# unoedge_v2.net
KiCad netlist of a schematic drawn in EAGLE
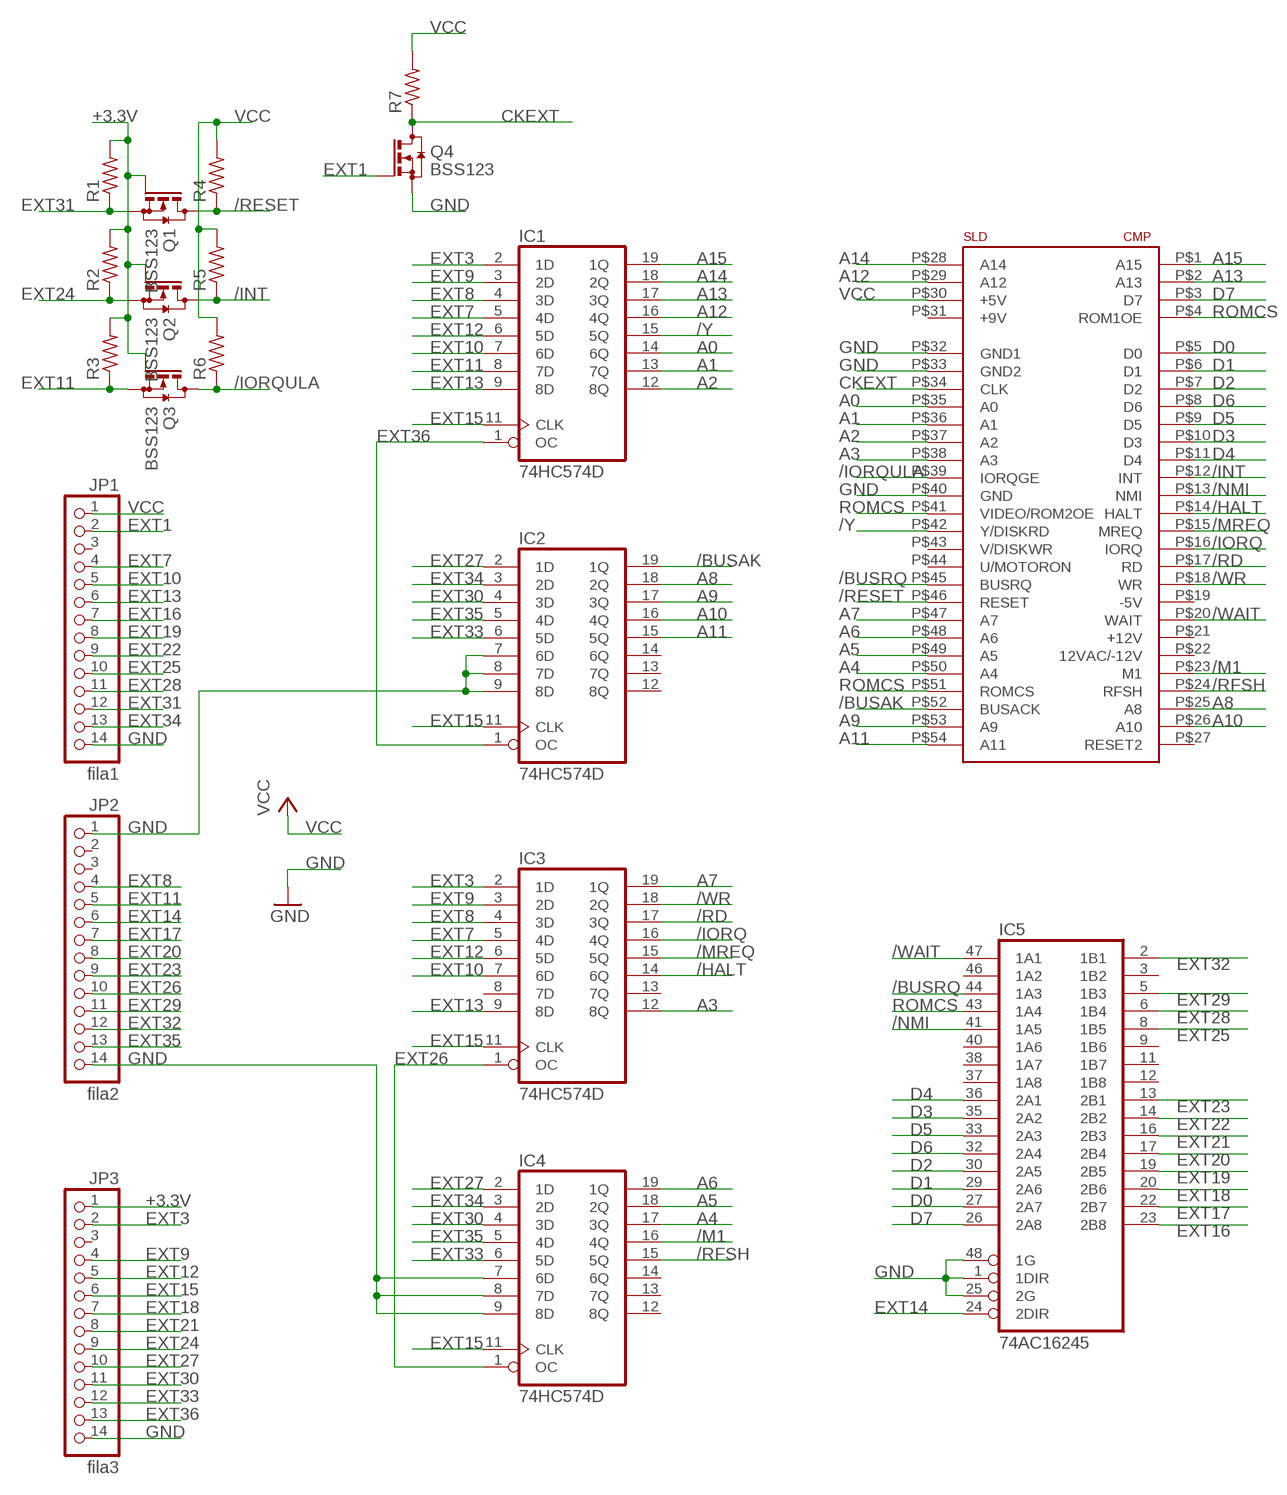
[diagram p0: schematic, sheet 1]

(export (version "E")
  (design (tool "Eeschema 10.0.6"))
  (components
    (comp (ref "IC1")
      (value "74HC574D")
      (footprint "eagle-import:SO20W")
      (libsource (lib "eagle-import") (part "74574DHC"))
    )
    (comp (ref "IC2")
      (value "74HC574D")
      (footprint "eagle-import:SO20W")
      (libsource (lib "eagle-import") (part "74574DHC"))
    )
    (comp (ref "IC3")
      (value "74HC574D")
      (footprint "eagle-import:SO20W")
      (libsource (lib "eagle-import") (part "74574DHC"))
    )
    (comp (ref "IC4")
      (value "74HC574D")
      (footprint "eagle-import:SO20W")
      (libsource (lib "eagle-import") (part "74574DHC"))
    )
    (comp (ref "IC5")
      (value "74AC16245")
      (footprint "eagle-import:SSOP48DL")
      (libsource (lib "eagle-import") (part "74AC16245"))
    )
    (comp (ref "JP1")
      (value "fila1")
      (footprint "eagle-import:1X14")
      (libsource (lib "eagle-import") (part "PINHD-1X14"))
    )
    (comp (ref "JP2")
      (value "fila2")
      (footprint "eagle-import:1X14")
      (libsource (lib "eagle-import") (part "PINHD-1X14"))
    )
    (comp (ref "JP3")
      (value "fila3")
      (footprint "eagle-import:1X14")
      (libsource (lib "eagle-import") (part "PINHD-1X14"))
    )
    (comp (ref "Q1")
      (value "BSS123")
      (footprint "eagle-import:SOT23")
      (libsource (lib "eagle-import") (part "BSS123"))
    )
    (comp (ref "Q2")
      (value "BSS123")
      (footprint "eagle-import:SOT23")
      (libsource (lib "eagle-import") (part "BSS123"))
    )
    (comp (ref "Q3")
      (value "BSS123")
      (footprint "eagle-import:SOT23")
      (libsource (lib "eagle-import") (part "BSS123"))
    )
    (comp (ref "Q4")
      (value "BSS123")
      (footprint "eagle-import:SOT23")
      (libsource (lib "eagle-import") (part "BSS123"))
    )
    (comp (ref "R1")
      (value "R-US_M0805")
      (footprint "eagle-import:M0805")
      (libsource (lib "eagle-import") (part "R-US_M0805"))
    )
    (comp (ref "R2")
      (value "R-US_M0805")
      (footprint "eagle-import:M0805")
      (libsource (lib "eagle-import") (part "R-US_M0805"))
    )
    (comp (ref "R3")
      (value "R-US_M0805")
      (footprint "eagle-import:M0805")
      (libsource (lib "eagle-import") (part "R-US_M0805"))
    )
    (comp (ref "R4")
      (value "R-US_M0805")
      (footprint "eagle-import:M0805")
      (libsource (lib "eagle-import") (part "R-US_M0805"))
    )
    (comp (ref "R5")
      (value "R-US_M0805")
      (footprint "eagle-import:M0805")
      (libsource (lib "eagle-import") (part "R-US_M0805"))
    )
    (comp (ref "R6")
      (value "R-US_M0805")
      (footprint "eagle-import:M0805")
      (libsource (lib "eagle-import") (part "R-US_M0805"))
    )
    (comp (ref "R7")
      (value "R-US_M0805")
      (footprint "eagle-import:M0805")
      (libsource (lib "eagle-import") (part "R-US_M0805"))
    )
    (comp (ref "U$2")
      (value "CONECTOR_EDGE_LADO_SPECTRUM")
      (footprint "eagle-import:CONECTOR_LADO_SPECTRUM")
      (libsource (lib "eagle-import") (part "CONECTOR_EDGE_LADO_SPECTRUM"))
    )
  )
  (nets
    (net (code "1") (name "/+3.3V") (class "Default")
      (node (ref "JP3") (pin "1") (pinfunction "1_1") (pintype "passive"))
      (node (ref "Q1") (pin "1") (pinfunction "G_1") (pintype "passive"))
      (node (ref "Q2") (pin "1") (pinfunction "G_1") (pintype "passive"))
      (node (ref "Q3") (pin "1") (pinfunction "G_1") (pintype "passive"))
      (node (ref "R1") (pin "2") (pinfunction "2_2") (pintype "passive"))
      (node (ref "R2") (pin "2") (pinfunction "2_2") (pintype "passive"))
      (node (ref "R3") (pin "2") (pinfunction "2_2") (pintype "passive"))
    )
    (net (code "2") (name "/A0") (class "Default")
      (node (ref "IC1") (pin "14") (pinfunction "6Q_14") (pintype "tri_state"))
      (node (ref "U$2") (pin "P$35") (pinfunction "A0_P$35") (pintype "bidirectional"))
    )
    (net (code "3") (name "/A1") (class "Default")
      (node (ref "IC1") (pin "13") (pinfunction "7Q_13") (pintype "tri_state"))
      (node (ref "U$2") (pin "P$36") (pinfunction "A1_P$36") (pintype "bidirectional"))
    )
    (net (code "4") (name "/A2") (class "Default")
      (node (ref "IC1") (pin "12") (pinfunction "8Q_12") (pintype "tri_state"))
      (node (ref "U$2") (pin "P$37") (pinfunction "A2_P$37") (pintype "bidirectional"))
    )
    (net (code "5") (name "/A3") (class "Default")
      (node (ref "IC3") (pin "12") (pinfunction "8Q_12") (pintype "tri_state"))
      (node (ref "U$2") (pin "P$38") (pinfunction "A3_P$38") (pintype "bidirectional"))
    )
    (net (code "6") (name "/A4") (class "Default")
      (node (ref "IC4") (pin "17") (pinfunction "3Q_17") (pintype "tri_state"))
      (node (ref "U$2") (pin "P$50") (pinfunction "A4_P$50") (pintype "bidirectional"))
    )
    (net (code "7") (name "/A5") (class "Default")
      (node (ref "IC4") (pin "18") (pinfunction "2Q_18") (pintype "tri_state"))
      (node (ref "U$2") (pin "P$49") (pinfunction "A5_P$49") (pintype "bidirectional"))
    )
    (net (code "8") (name "/A6") (class "Default")
      (node (ref "IC4") (pin "19") (pinfunction "1Q_19") (pintype "tri_state"))
      (node (ref "U$2") (pin "P$48") (pinfunction "A6_P$48") (pintype "bidirectional"))
    )
    (net (code "9") (name "/A7") (class "Default")
      (node (ref "IC3") (pin "19") (pinfunction "1Q_19") (pintype "tri_state"))
      (node (ref "U$2") (pin "P$47") (pinfunction "A7_P$47") (pintype "bidirectional"))
    )
    (net (code "10") (name "/A8") (class "Default")
      (node (ref "IC2") (pin "18") (pinfunction "2Q_18") (pintype "tri_state"))
      (node (ref "U$2") (pin "P$25") (pinfunction "A8_P$25") (pintype "bidirectional"))
    )
    (net (code "11") (name "/A9") (class "Default")
      (node (ref "IC2") (pin "17") (pinfunction "3Q_17") (pintype "tri_state"))
      (node (ref "U$2") (pin "P$53") (pinfunction "A9_P$53") (pintype "bidirectional"))
    )
    (net (code "12") (name "/A10") (class "Default")
      (node (ref "IC2") (pin "16") (pinfunction "4Q_16") (pintype "tri_state"))
      (node (ref "U$2") (pin "P$26") (pinfunction "A10_P$26") (pintype "bidirectional"))
    )
    (net (code "13") (name "/A11") (class "Default")
      (node (ref "IC2") (pin "15") (pinfunction "5Q_15") (pintype "tri_state"))
      (node (ref "U$2") (pin "P$54") (pinfunction "A11_P$54") (pintype "bidirectional"))
    )
    (net (code "14") (name "/A12") (class "Default")
      (node (ref "IC1") (pin "16") (pinfunction "4Q_16") (pintype "tri_state"))
      (node (ref "U$2") (pin "P$29") (pinfunction "A12_P$29") (pintype "bidirectional"))
    )
    (net (code "15") (name "/A13") (class "Default")
      (node (ref "IC1") (pin "17") (pinfunction "3Q_17") (pintype "tri_state"))
      (node (ref "U$2") (pin "P$2") (pinfunction "A13_P$2") (pintype "bidirectional"))
    )
    (net (code "16") (name "/A14") (class "Default")
      (node (ref "IC1") (pin "18") (pinfunction "2Q_18") (pintype "tri_state"))
      (node (ref "U$2") (pin "P$28") (pinfunction "A14_P$28") (pintype "bidirectional"))
    )
    (net (code "17") (name "/A15") (class "Default")
      (node (ref "IC1") (pin "19") (pinfunction "1Q_19") (pintype "tri_state"))
      (node (ref "U$2") (pin "P$1") (pinfunction "A15_P$1") (pintype "bidirectional"))
    )
    (net (code "18") (name "/CKEXT") (class "Default")
      (node (ref "Q4") (pin "3") (pinfunction "D_3") (pintype "passive"))
      (node (ref "R7") (pin "1") (pinfunction "1_1") (pintype "passive"))
      (node (ref "U$2") (pin "P$34") (pinfunction "CLK_P$34") (pintype "bidirectional"))
    )
    (net (code "19") (name "/D0") (class "Default")
      (node (ref "IC5") (pin "27") (pinfunction "2A7_27") (pintype "bidirectional"))
      (node (ref "U$2") (pin "P$5") (pinfunction "D0_P$5") (pintype "bidirectional"))
    )
    (net (code "20") (name "/D1") (class "Default")
      (node (ref "IC5") (pin "29") (pinfunction "2A6_29") (pintype "bidirectional"))
      (node (ref "U$2") (pin "P$6") (pinfunction "D1_P$6") (pintype "bidirectional"))
    )
    (net (code "21") (name "/D2") (class "Default")
      (node (ref "IC5") (pin "30") (pinfunction "2A5_30") (pintype "bidirectional"))
      (node (ref "U$2") (pin "P$7") (pinfunction "D2_P$7") (pintype "bidirectional"))
    )
    (net (code "22") (name "/D3") (class "Default")
      (node (ref "IC5") (pin "35") (pinfunction "2A2_35") (pintype "bidirectional"))
      (node (ref "U$2") (pin "P$10") (pinfunction "D3_P$10") (pintype "bidirectional"))
    )
    (net (code "23") (name "/D4") (class "Default")
      (node (ref "IC5") (pin "36") (pinfunction "2A1_36") (pintype "bidirectional"))
      (node (ref "U$2") (pin "P$11") (pinfunction "D4_P$11") (pintype "bidirectional"))
    )
    (net (code "24") (name "/D5") (class "Default")
      (node (ref "IC5") (pin "33") (pinfunction "2A3_33") (pintype "bidirectional"))
      (node (ref "U$2") (pin "P$9") (pinfunction "D5_P$9") (pintype "bidirectional"))
    )
    (net (code "25") (name "/D6") (class "Default")
      (node (ref "IC5") (pin "32") (pinfunction "2A4_32") (pintype "bidirectional"))
      (node (ref "U$2") (pin "P$8") (pinfunction "D6_P$8") (pintype "bidirectional"))
    )
    (net (code "26") (name "/D7") (class "Default")
      (node (ref "IC5") (pin "26") (pinfunction "2A8_26") (pintype "bidirectional"))
      (node (ref "U$2") (pin "P$3") (pinfunction "D7_P$3") (pintype "bidirectional"))
    )
    (net (code "27") (name "/EXT1") (class "Default")
      (node (ref "JP1") (pin "2") (pinfunction "2_2") (pintype "passive"))
      (node (ref "Q4") (pin "1") (pinfunction "G_1") (pintype "passive"))
    )
    (net (code "28") (name "/EXT3") (class "Default")
      (node (ref "IC1") (pin "2") (pinfunction "1D_2") (pintype "input"))
      (node (ref "IC3") (pin "2") (pinfunction "1D_2") (pintype "input"))
      (node (ref "JP3") (pin "2") (pinfunction "2_2") (pintype "passive"))
    )
    (net (code "29") (name "/EXT7") (class "Default")
      (node (ref "IC1") (pin "5") (pinfunction "4D_5") (pintype "input"))
      (node (ref "IC3") (pin "5") (pinfunction "4D_5") (pintype "input"))
      (node (ref "JP1") (pin "4") (pinfunction "4_4") (pintype "passive"))
    )
    (net (code "30") (name "/EXT8") (class "Default")
      (node (ref "IC1") (pin "4") (pinfunction "3D_4") (pintype "input"))
      (node (ref "IC3") (pin "4") (pinfunction "3D_4") (pintype "input"))
      (node (ref "JP2") (pin "4") (pinfunction "4_4") (pintype "passive"))
    )
    (net (code "31") (name "/EXT9") (class "Default")
      (node (ref "IC1") (pin "3") (pinfunction "2D_3") (pintype "input"))
      (node (ref "IC3") (pin "3") (pinfunction "2D_3") (pintype "input"))
      (node (ref "JP3") (pin "4") (pinfunction "4_4") (pintype "passive"))
    )
    (net (code "32") (name "/EXT10") (class "Default")
      (node (ref "IC1") (pin "7") (pinfunction "6D_7") (pintype "input"))
      (node (ref "IC3") (pin "7") (pinfunction "6D_7") (pintype "input"))
      (node (ref "JP1") (pin "5") (pinfunction "5_5") (pintype "passive"))
    )
    (net (code "33") (name "/EXT11") (class "Default")
      (node (ref "IC1") (pin "8") (pinfunction "7D_8") (pintype "input"))
      (node (ref "JP2") (pin "5") (pinfunction "5_5") (pintype "passive"))
      (node (ref "Q3") (pin "2") (pinfunction "S_2") (pintype "passive"))
      (node (ref "R3") (pin "1") (pinfunction "1_1") (pintype "passive"))
    )
    (net (code "34") (name "/EXT12") (class "Default")
      (node (ref "IC1") (pin "6") (pinfunction "5D_6") (pintype "input"))
      (node (ref "IC3") (pin "6") (pinfunction "5D_6") (pintype "input"))
      (node (ref "JP3") (pin "5") (pinfunction "5_5") (pintype "passive"))
    )
    (net (code "35") (name "/EXT13") (class "Default")
      (node (ref "IC1") (pin "9") (pinfunction "8D_9") (pintype "input"))
      (node (ref "IC3") (pin "9") (pinfunction "8D_9") (pintype "input"))
      (node (ref "JP1") (pin "6") (pinfunction "6_6") (pintype "passive"))
    )
    (net (code "36") (name "/EXT14") (class "Default")
      (node (ref "IC5") (pin "24") (pinfunction "2DIR_24") (pintype "input"))
      (node (ref "JP2") (pin "6") (pinfunction "6_6") (pintype "passive"))
    )
    (net (code "37") (name "/EXT15") (class "Default")
      (node (ref "IC1") (pin "11") (pinfunction "CLK_11") (pintype "input"))
      (node (ref "IC2") (pin "11") (pinfunction "CLK_11") (pintype "input"))
      (node (ref "IC3") (pin "11") (pinfunction "CLK_11") (pintype "input"))
      (node (ref "IC4") (pin "11") (pinfunction "CLK_11") (pintype "input"))
      (node (ref "JP3") (pin "6") (pinfunction "6_6") (pintype "passive"))
    )
    (net (code "38") (name "/EXT16") (class "Default")
      (node (ref "IC5") (pin "23") (pinfunction "2B8_23") (pintype "bidirectional"))
      (node (ref "JP1") (pin "7") (pinfunction "7_7") (pintype "passive"))
    )
    (net (code "39") (name "/EXT17") (class "Default")
      (node (ref "IC5") (pin "22") (pinfunction "2B7_22") (pintype "bidirectional"))
      (node (ref "JP2") (pin "7") (pinfunction "7_7") (pintype "passive"))
    )
    (net (code "40") (name "/EXT18") (class "Default")
      (node (ref "IC5") (pin "20") (pinfunction "2B6_20") (pintype "bidirectional"))
      (node (ref "JP3") (pin "7") (pinfunction "7_7") (pintype "passive"))
    )
    (net (code "41") (name "/EXT19") (class "Default")
      (node (ref "IC5") (pin "19") (pinfunction "2B5_19") (pintype "bidirectional"))
      (node (ref "JP1") (pin "8") (pinfunction "8_8") (pintype "passive"))
    )
    (net (code "42") (name "/EXT20") (class "Default")
      (node (ref "IC5") (pin "17") (pinfunction "2B4_17") (pintype "bidirectional"))
      (node (ref "JP2") (pin "8") (pinfunction "8_8") (pintype "passive"))
    )
    (net (code "43") (name "/EXT21") (class "Default")
      (node (ref "IC5") (pin "16") (pinfunction "2B3_16") (pintype "bidirectional"))
      (node (ref "JP3") (pin "8") (pinfunction "8_8") (pintype "passive"))
    )
    (net (code "44") (name "/EXT22") (class "Default")
      (node (ref "IC5") (pin "14") (pinfunction "2B2_14") (pintype "bidirectional"))
      (node (ref "JP1") (pin "9") (pinfunction "9_9") (pintype "passive"))
    )
    (net (code "45") (name "/EXT23") (class "Default")
      (node (ref "IC5") (pin "13") (pinfunction "2B1_13") (pintype "bidirectional"))
      (node (ref "JP2") (pin "9") (pinfunction "9_9") (pintype "passive"))
    )
    (net (code "46") (name "/EXT24") (class "Default")
      (node (ref "JP3") (pin "9") (pinfunction "9_9") (pintype "passive"))
      (node (ref "Q2") (pin "2") (pinfunction "S_2") (pintype "passive"))
      (node (ref "R2") (pin "1") (pinfunction "1_1") (pintype "passive"))
    )
    (net (code "47") (name "/EXT25") (class "Default")
      (node (ref "IC5") (pin "8") (pinfunction "1B5_8") (pintype "bidirectional"))
      (node (ref "JP1") (pin "10") (pinfunction "10_10") (pintype "passive"))
    )
    (net (code "48") (name "/EXT26") (class "Default")
      (node (ref "IC3") (pin "1") (pinfunction "OC_1") (pintype "input"))
      (node (ref "IC4") (pin "1") (pinfunction "OC_1") (pintype "input"))
      (node (ref "JP2") (pin "10") (pinfunction "10_10") (pintype "passive"))
    )
    (net (code "49") (name "/EXT27") (class "Default")
      (node (ref "IC2") (pin "2") (pinfunction "1D_2") (pintype "input"))
      (node (ref "IC4") (pin "2") (pinfunction "1D_2") (pintype "input"))
      (node (ref "JP3") (pin "10") (pinfunction "10_10") (pintype "passive"))
    )
    (net (code "50") (name "/EXT28") (class "Default")
      (node (ref "IC5") (pin "6") (pinfunction "1B4_6") (pintype "bidirectional"))
      (node (ref "JP1") (pin "11") (pinfunction "11_11") (pintype "passive"))
    )
    (net (code "51") (name "/EXT29") (class "Default")
      (node (ref "IC5") (pin "5") (pinfunction "1B3_5") (pintype "bidirectional"))
      (node (ref "JP2") (pin "11") (pinfunction "11_11") (pintype "passive"))
    )
    (net (code "52") (name "/EXT30") (class "Default")
      (node (ref "IC2") (pin "4") (pinfunction "3D_4") (pintype "input"))
      (node (ref "IC4") (pin "4") (pinfunction "3D_4") (pintype "input"))
      (node (ref "JP3") (pin "11") (pinfunction "11_11") (pintype "passive"))
    )
    (net (code "53") (name "/EXT31") (class "Default")
      (node (ref "JP1") (pin "12") (pinfunction "12_12") (pintype "passive"))
      (node (ref "Q1") (pin "2") (pinfunction "S_2") (pintype "passive"))
      (node (ref "R1") (pin "1") (pinfunction "1_1") (pintype "passive"))
    )
    (net (code "54") (name "/EXT32") (class "Default")
      (node (ref "IC5") (pin "2") (pinfunction "1B1_2") (pintype "bidirectional"))
      (node (ref "JP2") (pin "12") (pinfunction "12_12") (pintype "passive"))
    )
    (net (code "55") (name "/EXT33") (class "Default")
      (node (ref "IC2") (pin "6") (pinfunction "5D_6") (pintype "input"))
      (node (ref "IC4") (pin "6") (pinfunction "5D_6") (pintype "input"))
      (node (ref "JP3") (pin "12") (pinfunction "12_12") (pintype "passive"))
    )
    (net (code "56") (name "/EXT34") (class "Default")
      (node (ref "IC2") (pin "3") (pinfunction "2D_3") (pintype "input"))
      (node (ref "IC4") (pin "3") (pinfunction "2D_3") (pintype "input"))
      (node (ref "JP1") (pin "13") (pinfunction "13_13") (pintype "passive"))
    )
    (net (code "57") (name "/EXT35") (class "Default")
      (node (ref "IC2") (pin "5") (pinfunction "4D_5") (pintype "input"))
      (node (ref "IC4") (pin "5") (pinfunction "4D_5") (pintype "input"))
      (node (ref "JP2") (pin "13") (pinfunction "13_13") (pintype "passive"))
    )
    (net (code "58") (name "/EXT36") (class "Default")
      (node (ref "IC1") (pin "1") (pinfunction "OC_1") (pintype "input"))
      (node (ref "IC2") (pin "1") (pinfunction "OC_1") (pintype "input"))
      (node (ref "JP3") (pin "13") (pinfunction "13_13") (pintype "passive"))
    )
    (net (code "59") (name "/ROMCS") (class "Default")
      (node (ref "IC5") (pin "43") (pinfunction "1A4_43") (pintype "bidirectional"))
      (node (ref "U$2") (pin "P$4") (pinfunction "ROM1OE_P$4") (pintype "bidirectional"))
      (node (ref "U$2") (pin "P$41") (pinfunction "VIDEO/ROM2OE_P$41") (pintype "bidirectional"))
      (node (ref "U$2") (pin "P$51") (pinfunction "ROMCS_P$51") (pintype "bidirectional"))
    )
    (net (code "60") (name "/{slash}BUSAK") (class "Default")
      (node (ref "IC2") (pin "19") (pinfunction "1Q_19") (pintype "tri_state"))
      (node (ref "U$2") (pin "P$52") (pinfunction "BUSACK_P$52") (pintype "bidirectional"))
    )
    (net (code "61") (name "/{slash}BUSRQ") (class "Default")
      (node (ref "IC5") (pin "44") (pinfunction "1A3_44") (pintype "bidirectional"))
      (node (ref "U$2") (pin "P$45") (pinfunction "BUSRQ_P$45") (pintype "bidirectional"))
    )
    (net (code "62") (name "/{slash}HALT") (class "Default")
      (node (ref "IC3") (pin "14") (pinfunction "6Q_14") (pintype "tri_state"))
      (node (ref "U$2") (pin "P$14") (pinfunction "HALT_P$14") (pintype "bidirectional"))
    )
    (net (code "63") (name "/{slash}INT") (class "Default")
      (node (ref "Q2") (pin "3") (pinfunction "D_3") (pintype "passive"))
      (node (ref "R5") (pin "1") (pinfunction "1_1") (pintype "passive"))
      (node (ref "U$2") (pin "P$12") (pinfunction "INT_P$12") (pintype "bidirectional"))
    )
    (net (code "64") (name "/{slash}IORQ") (class "Default")
      (node (ref "IC3") (pin "16") (pinfunction "4Q_16") (pintype "tri_state"))
      (node (ref "U$2") (pin "P$16") (pinfunction "IORQ_P$16") (pintype "bidirectional"))
    )
    (net (code "65") (name "/{slash}IORQULA") (class "Default")
      (node (ref "Q3") (pin "3") (pinfunction "D_3") (pintype "passive"))
      (node (ref "R6") (pin "1") (pinfunction "1_1") (pintype "passive"))
      (node (ref "U$2") (pin "P$39") (pinfunction "IORQGE_P$39") (pintype "bidirectional"))
    )
    (net (code "66") (name "/{slash}M1") (class "Default")
      (node (ref "IC4") (pin "16") (pinfunction "4Q_16") (pintype "tri_state"))
      (node (ref "U$2") (pin "P$23") (pinfunction "M1_P$23") (pintype "bidirectional"))
    )
    (net (code "67") (name "/{slash}MREQ") (class "Default")
      (node (ref "IC3") (pin "15") (pinfunction "5Q_15") (pintype "tri_state"))
      (node (ref "U$2") (pin "P$15") (pinfunction "MREQ_P$15") (pintype "bidirectional"))
    )
    (net (code "68") (name "/{slash}NMI") (class "Default")
      (node (ref "IC5") (pin "41") (pinfunction "1A5_41") (pintype "bidirectional"))
      (node (ref "U$2") (pin "P$13") (pinfunction "NMI_P$13") (pintype "bidirectional"))
    )
    (net (code "69") (name "/{slash}RD") (class "Default")
      (node (ref "IC3") (pin "17") (pinfunction "3Q_17") (pintype "tri_state"))
      (node (ref "U$2") (pin "P$17") (pinfunction "RD_P$17") (pintype "bidirectional"))
    )
    (net (code "70") (name "/{slash}RESET") (class "Default")
      (node (ref "Q1") (pin "3") (pinfunction "D_3") (pintype "passive"))
      (node (ref "R4") (pin "1") (pinfunction "1_1") (pintype "passive"))
      (node (ref "U$2") (pin "P$46") (pinfunction "RESET_P$46") (pintype "bidirectional"))
    )
    (net (code "71") (name "/{slash}RFSH") (class "Default")
      (node (ref "IC4") (pin "15") (pinfunction "5Q_15") (pintype "tri_state"))
      (node (ref "U$2") (pin "P$24") (pinfunction "RFSH_P$24") (pintype "bidirectional"))
    )
    (net (code "72") (name "/{slash}WAIT") (class "Default")
      (node (ref "IC5") (pin "47") (pinfunction "1A1_47") (pintype "bidirectional"))
      (node (ref "U$2") (pin "P$20") (pinfunction "WAIT_P$20") (pintype "bidirectional"))
    )
    (net (code "73") (name "/{slash}WR") (class "Default")
      (node (ref "IC3") (pin "18") (pinfunction "2Q_18") (pintype "tri_state"))
      (node (ref "U$2") (pin "P$18") (pinfunction "WR_P$18") (pintype "bidirectional"))
    )
    (net (code "74") (name "/{slash}Y") (class "Default")
      (node (ref "IC1") (pin "15") (pinfunction "5Q_15") (pintype "tri_state"))
      (node (ref "U$2") (pin "P$42") (pinfunction "Y/DISKRD_P$42") (pintype "bidirectional"))
    )
    (net (code "75") (name "GND") (class "Default")
      (node (ref "IC2") (pin "7") (pinfunction "6D_7") (pintype "input"))
      (node (ref "IC2") (pin "8") (pinfunction "7D_8") (pintype "input"))
      (node (ref "IC2") (pin "9") (pinfunction "8D_9") (pintype "input"))
      (node (ref "IC4") (pin "7") (pinfunction "6D_7") (pintype "input"))
      (node (ref "IC4") (pin "8") (pinfunction "7D_8") (pintype "input"))
      (node (ref "IC4") (pin "9") (pinfunction "8D_9") (pintype "input"))
      (node (ref "IC5") (pin "1") (pinfunction "1DIR_1") (pintype "input"))
      (node (ref "IC5") (pin "25") (pinfunction "2G_25") (pintype "input"))
      (node (ref "IC5") (pin "48") (pinfunction "1G_48") (pintype "input"))
      (node (ref "JP1") (pin "14") (pinfunction "14_14") (pintype "passive"))
      (node (ref "JP2") (pin "1") (pinfunction "1_1") (pintype "passive"))
      (node (ref "JP2") (pin "14") (pinfunction "14_14") (pintype "passive"))
      (node (ref "JP3") (pin "14") (pinfunction "14_14") (pintype "passive"))
      (node (ref "Q4") (pin "2") (pinfunction "S_2") (pintype "passive"))
      (node (ref "U$2") (pin "P$32") (pinfunction "GND1_P$32") (pintype "bidirectional"))
      (node (ref "U$2") (pin "P$33") (pinfunction "GND2_P$33") (pintype "bidirectional"))
      (node (ref "U$2") (pin "P$40") (pinfunction "GND_P$40") (pintype "bidirectional"))
    )
    (net (code "76") (name "VCC") (class "Default")
      (node (ref "JP1") (pin "1") (pinfunction "1_1") (pintype "passive"))
      (node (ref "R4") (pin "2") (pinfunction "2_2") (pintype "passive"))
      (node (ref "R5") (pin "2") (pinfunction "2_2") (pintype "passive"))
      (node (ref "R6") (pin "2") (pinfunction "2_2") (pintype "passive"))
      (node (ref "R7") (pin "2") (pinfunction "2_2") (pintype "passive"))
      (node (ref "U$2") (pin "P$30") (pinfunction "+5V_P$30") (pintype "bidirectional"))
    )
    (net (code "77") (name "unconnected-(IC2A-6Q-Pad14)") (class "Default")
      (node (ref "IC2") (pin "14") (pinfunction "6Q_14") (pintype "tri_state"))
    )
    (net (code "78") (name "unconnected-(IC2A-7Q-Pad13)") (class "Default")
      (node (ref "IC2") (pin "13") (pinfunction "7Q_13") (pintype "tri_state"))
    )
    (net (code "79") (name "unconnected-(IC2A-8Q-Pad12)") (class "Default")
      (node (ref "IC2") (pin "12") (pinfunction "8Q_12") (pintype "tri_state"))
    )
    (net (code "80") (name "unconnected-(IC3A-7D-Pad8)") (class "Default")
      (node (ref "IC3") (pin "8") (pinfunction "7D_8") (pintype "input"))
    )
    (net (code "81") (name "unconnected-(IC3A-7Q-Pad13)") (class "Default")
      (node (ref "IC3") (pin "13") (pinfunction "7Q_13") (pintype "tri_state"))
    )
    (net (code "82") (name "unconnected-(IC4A-6Q-Pad14)") (class "Default")
      (node (ref "IC4") (pin "14") (pinfunction "6Q_14") (pintype "tri_state"))
    )
    (net (code "83") (name "unconnected-(IC4A-7Q-Pad13)") (class "Default")
      (node (ref "IC4") (pin "13") (pinfunction "7Q_13") (pintype "tri_state"))
    )
    (net (code "84") (name "unconnected-(IC4A-8Q-Pad12)") (class "Default")
      (node (ref "IC4") (pin "12") (pinfunction "8Q_12") (pintype "tri_state"))
    )
    (net (code "85") (name "unconnected-(IC5A-1A2-Pad46)") (class "Default")
      (node (ref "IC5") (pin "46") (pinfunction "1A2_46") (pintype "bidirectional"))
    )
    (net (code "86") (name "unconnected-(IC5A-1A6-Pad40)") (class "Default")
      (node (ref "IC5") (pin "40") (pinfunction "1A6_40") (pintype "bidirectional"))
    )
    (net (code "87") (name "unconnected-(IC5A-1A7-Pad38)") (class "Default")
      (node (ref "IC5") (pin "38") (pinfunction "1A7_38") (pintype "bidirectional"))
    )
    (net (code "88") (name "unconnected-(IC5A-1A8-Pad37)") (class "Default")
      (node (ref "IC5") (pin "37") (pinfunction "1A8_37") (pintype "bidirectional"))
    )
    (net (code "89") (name "unconnected-(IC5A-1B2-Pad3)") (class "Default")
      (node (ref "IC5") (pin "3") (pinfunction "1B2_3") (pintype "bidirectional"))
    )
    (net (code "90") (name "unconnected-(IC5A-1B6-Pad9)") (class "Default")
      (node (ref "IC5") (pin "9") (pinfunction "1B6_9") (pintype "bidirectional"))
    )
    (net (code "91") (name "unconnected-(IC5A-1B7-Pad11)") (class "Default")
      (node (ref "IC5") (pin "11") (pinfunction "1B7_11") (pintype "bidirectional"))
    )
    (net (code "92") (name "unconnected-(IC5A-1B8-Pad12)") (class "Default")
      (node (ref "IC5") (pin "12") (pinfunction "1B8_12") (pintype "bidirectional"))
    )
    (net (code "93") (name "unconnected-(JP1-Pad3)") (class "Default")
      (node (ref "JP1") (pin "3") (pinfunction "3_3") (pintype "passive"))
    )
    (net (code "94") (name "unconnected-(JP2-Pad2)") (class "Default")
      (node (ref "JP2") (pin "2") (pinfunction "2_2") (pintype "passive"))
    )
    (net (code "95") (name "unconnected-(JP2-Pad3)") (class "Default")
      (node (ref "JP2") (pin "3") (pinfunction "3_3") (pintype "passive"))
    )
    (net (code "96") (name "unconnected-(JP3-Pad3)") (class "Default")
      (node (ref "JP3") (pin "3") (pinfunction "3_3") (pintype "passive"))
    )
    (net (code "97") (name "unconnected-(U$2-+9V-PadP$31)") (class "Default")
      (node (ref "U$2") (pin "P$31") (pinfunction "+9V_P$31") (pintype "bidirectional"))
    )
    (net (code "98") (name "unconnected-(U$2-+12V-PadP$21)") (class "Default")
      (node (ref "U$2") (pin "P$21") (pinfunction "+12V_P$21") (pintype "bidirectional"))
    )
    (net (code "99") (name "unconnected-(U$2--5V-PadP$19)") (class "Default")
      (node (ref "U$2") (pin "P$19") (pinfunction "-5V_P$19") (pintype "bidirectional"))
    )
    (net (code "100") (name "unconnected-(U$2-12VAC{slash}-12V-PadP$22)") (class "Default")
      (node (ref "U$2") (pin "P$22") (pinfunction "12VAC/-12V_P$22") (pintype "bidirectional"))
    )
    (net (code "101") (name "unconnected-(U$2-RESET2-PadP$27)") (class "Default")
      (node (ref "U$2") (pin "P$27") (pinfunction "RESET2_P$27") (pintype "bidirectional"))
    )
    (net (code "102") (name "unconnected-(U$2-U{slash}MOTORON-PadP$44)") (class "Default")
      (node (ref "U$2") (pin "P$44") (pinfunction "U/MOTORON_P$44") (pintype "bidirectional"))
    )
    (net (code "103") (name "unconnected-(U$2-V{slash}DISKWR-PadP$43)") (class "Default")
      (node (ref "U$2") (pin "P$43") (pinfunction "V/DISKWR_P$43") (pintype "bidirectional"))
    )
  )
)
